# 9V_Converter.net
KiCad netlist of a schematic drawn in Altium Designer
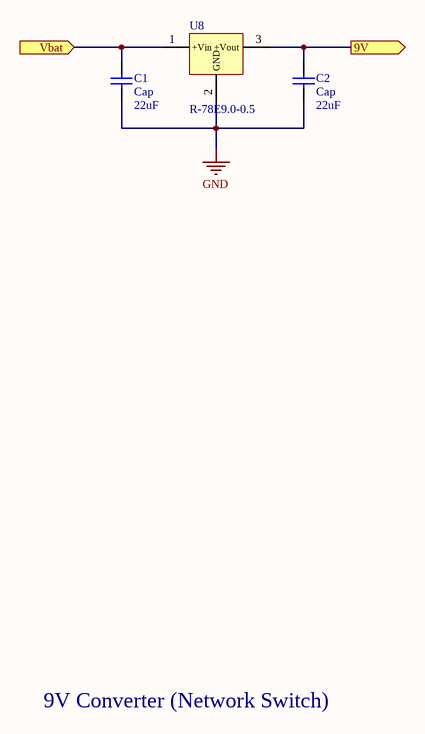
[diagram p0: 9V_Converter.SchDoc]

(export (version "E")
  (design (tool "Eeschema 10.0.6"))
  (components
    (comp (ref "C1")
      (value "Cap")
      (footprint "C1206")
      (description "Capacitor (Semiconductor SIM Model)")
      (fields (field (name "ALTIUM_VALUE") "22uF") (field (name "PUBLISHER") "Altium Limited"))
      (libsource (lib "Miscellaneous Devices") (part "Cap Semi"))
    )
    (comp (ref "C2")
      (value "Cap")
      (footprint "C1206")
      (description "Capacitor (Semiconductor SIM Model)")
      (fields (field (name "ALTIUM_VALUE") "22uF") (field (name "PUBLISHER") "Altium Limited"))
      (libsource (lib "Miscellaneous Devices") (part "Cap Semi"))
    )
    (comp (ref "U8")
      (value "R-78E9.0-0.5")
      (footprint "R-78Exx-0.5")
      (description "0.5A DC/DC Voltage Converter")
      (libsource (lib "Power_Embedded_Board_Library") (part "R-78Exx-0.5"))
    )
  )
  (nets
    (net (code "1") (name "/9V") (class "Default")
      (node (ref "C2") (pin "2") (pinfunction "2_2") (pintype "passive"))
      (node (ref "U8") (pin "3") (pinfunction "+Vout_3") (pintype "passive"))
    )
    (net (code "2") (name "/Vbat") (class "Default")
      (node (ref "C1") (pin "2") (pinfunction "2_2") (pintype "passive"))
      (node (ref "U8") (pin "1") (pinfunction "+Vin_1") (pintype "passive"))
    )
    (net (code "3") (name "GND") (class "Default")
      (node (ref "C1") (pin "1") (pinfunction "1_1") (pintype "passive"))
      (node (ref "C2") (pin "1") (pinfunction "1_1") (pintype "passive"))
      (node (ref "U8") (pin "2") (pinfunction "GND_2") (pintype "passive"))
    )
  )
)
